# 24P_TO_15P_FPC_CSI_ADAPTER.net
KiCad netlist of a schematic drawn in Altium Designer
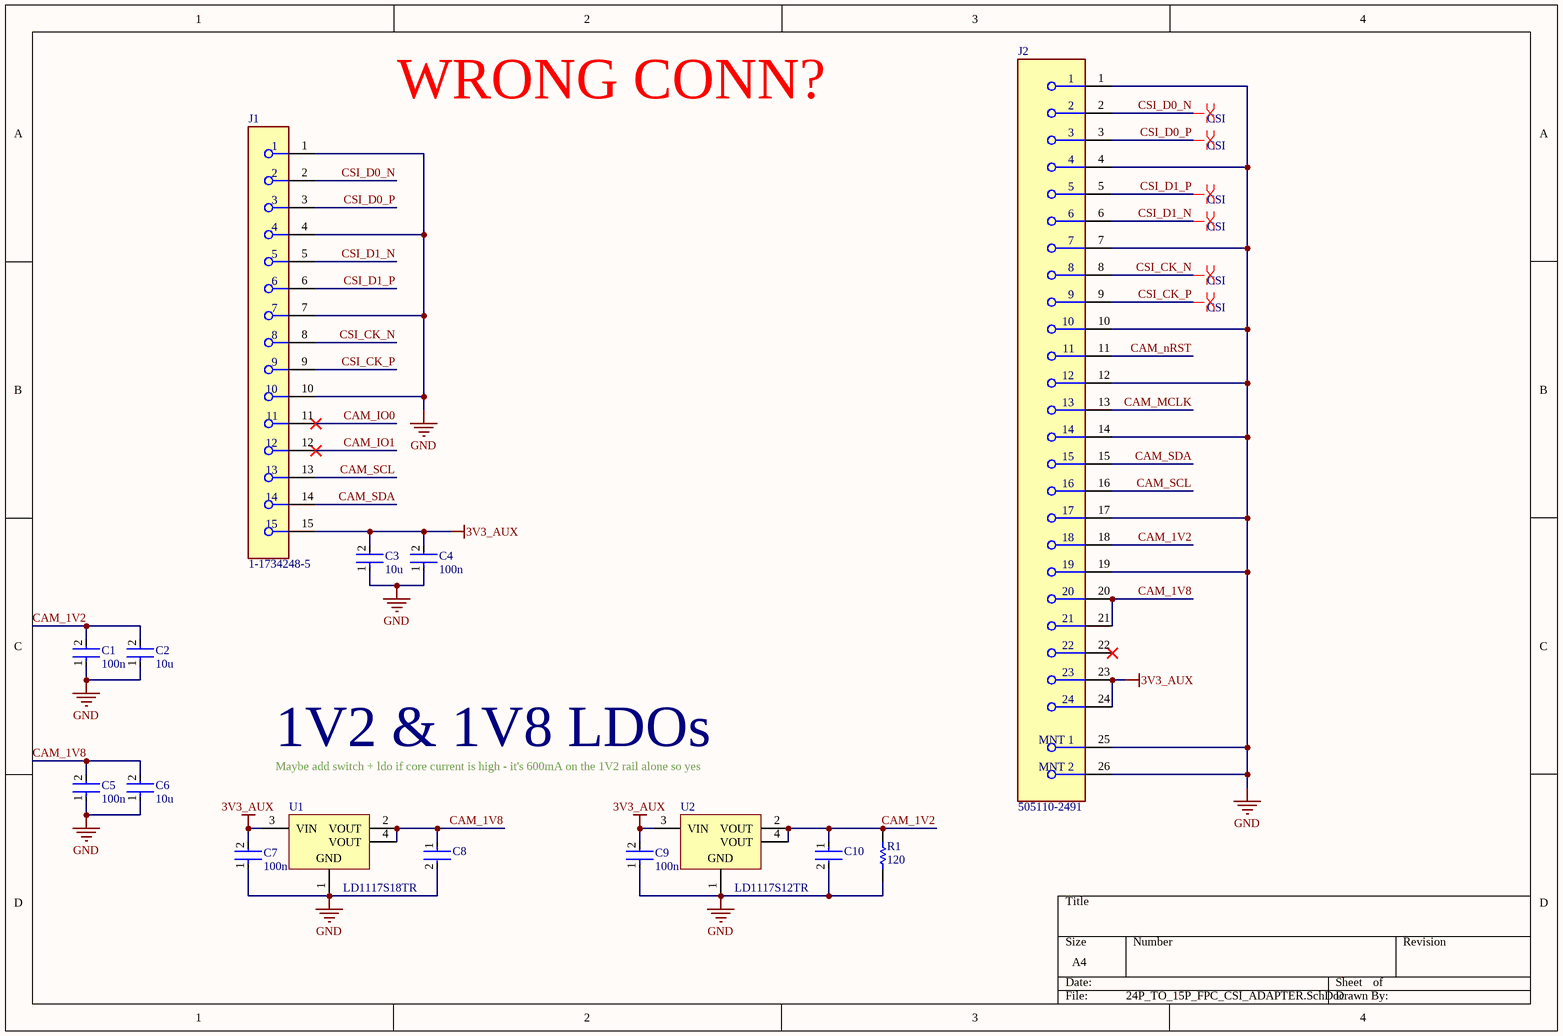
[diagram p0: 24P_TO_15P_FPC_CSI_ADAPTER.SchDoc]

(export (version "E")
  (design (tool "Eeschema 10.0.6"))
  (components
    (comp (ref "C1")
      (value "100n")
      (footprint "FP-0402-L_1_0_0_05-W_0_5-IPC_A")
      (description "LARGE PADS, 0402 CAP, CHANGE COMMENT TO MATCH REAL P/N")
      (libsource (lib "Space Concordia") (part "b4654b650e69147ec39a6b967a45e02"))
    )
    (comp (ref "C2")
      (value "10u")
      (footprint "FP-0402-L_1_0_0_05-W_0_5-IPC_A")
      (description "LARGE PADS, 0402 CAP, CHANGE COMMENT TO MATCH REAL P/N")
      (libsource (lib "Space Concordia") (part "b4654b650e69147ec39a6b967a45e02"))
    )
    (comp (ref "C3")
      (value "10u")
      (footprint "FP-0402-L_1_0_0_05-W_0_5-IPC_A")
      (description "LARGE PADS, 0402 CAP, CHANGE COMMENT TO MATCH REAL P/N")
      (libsource (lib "Space Concordia") (part "b4654b650e69147ec39a6b967a45e02"))
    )
    (comp (ref "C4")
      (value "100n")
      (footprint "FP-0402-L_1_0_0_05-W_0_5-IPC_A")
      (description "LARGE PADS, 0402 CAP, CHANGE COMMENT TO MATCH REAL P/N")
      (libsource (lib "Space Concordia") (part "b4654b650e69147ec39a6b967a45e02"))
    )
    (comp (ref "C5")
      (value "100n")
      (footprint "FP-0402-L_1_0_0_05-W_0_5-IPC_A")
      (description "LARGE PADS, 0402 CAP, CHANGE COMMENT TO MATCH REAL P/N")
      (libsource (lib "Space Concordia") (part "b4654b650e69147ec39a6b967a45e02"))
    )
    (comp (ref "C6")
      (value "10u")
      (footprint "FP-0402-L_1_0_0_05-W_0_5-IPC_A")
      (description "LARGE PADS, 0402 CAP, CHANGE COMMENT TO MATCH REAL P/N")
      (libsource (lib "Space Concordia") (part "b4654b650e69147ec39a6b967a45e02"))
    )
    (comp (ref "C7")
      (value "100n")
      (footprint "FP-0402-L_1_0_0_05-W_0_5-IPC_A")
      (description "LARGE PADS, 0402 CAP, CHANGE COMMENT TO MATCH REAL P/N")
      (libsource (lib "Space Concordia") (part "b4654b650e69147ec39a6b967a45e02"))
    )
    (comp (ref "C8")
      (value "GRM188R60J106ME47D")
      (footprint "FP-GRM188-0_1-e0_2_0_55-IPC_A")
      (description "Chip Multilayer Ceramic Capacitors for General Purpose, 0603, 10uF, X5R, 15%, 20%, 6.3V")
      (fields (field (name "VOLTAGE") "6.3V") (field (name "TOLERANCE") "20%"))
      (libsource (lib "Altium Content Vault") (part "02cd4be3c70576c341d710602a673aa"))
    )
    (comp (ref "C9")
      (value "100n")
      (footprint "FP-0402-L_1_0_0_05-W_0_5-IPC_A")
      (description "LARGE PADS, 0402 CAP, CHANGE COMMENT TO MATCH REAL P/N")
      (libsource (lib "Space Concordia") (part "b4654b650e69147ec39a6b967a45e02"))
    )
    (comp (ref "C10")
      (value "GRM188R60J106ME47D")
      (footprint "FP-GRM188-0_1-e0_2_0_55-IPC_A")
      (description "Chip Multilayer Ceramic Capacitors for General Purpose, 0603, 10uF, X5R, 15%, 20%, 6.3V")
      (fields (field (name "VOLTAGE") "6.3V") (field (name "TOLERANCE") "20%"))
      (libsource (lib "Altium Content Vault") (part "02cd4be3c70576c341d710602a673aa"))
    )
    (comp (ref "J1")
      (value "1-1734248-5")
      (footprint "FP-1-1734248-5-MFG")
      (description "CONN FPC VERT 15POS 1.00MM SMD")
      (fields
        (field (name "MANUFACTURER") "TE")
        (field (name "OCTOPART") "https://octopart.com/1-1734248-5-te+connectivity-40620898")
      )
      (libsource (lib "Altium Content Vault") (part "a0777be16b290adccad2a8f9338c195"))
    )
    (comp (ref "J2")
      (value "505110-2491")
      (footprint "FP-505110-2491-MFG")
      (description "CONN FFC/FPC BOTTOM 24P .5MM R/A")
      (libsource (lib "Altium Content Vault") (part "affe414c170fb6748ef65fd2752df84"))
    )
    (comp (ref "R1")
      (value "120")
      (footprint "R0603B")
      (description "Resistor")
      (libsource (lib "Space Concordia") (part "Resistor"))
    )
    (comp (ref "U1")
      (value "LD1117S18TR")
      (footprint "SOT-223_M")
      (description "Fixed Low Drop Positive Voltage Regulator, 1.8V, 4-Pin SOT-223, Tape and Reel")
      (libsource (lib "Altium Content Vault") (part "PM-REG-LD1117-SOT4"))
    )
    (comp (ref "U2")
      (value "LD1117S12TR")
      (footprint "SOT-223_M")
      (description "Fixed Low Drop Positive Voltage Regulator, 1.2V, 4-Pin SOT-223, Tape and Reel")
      (libsource (lib "Altium Content Vault") (part "PM-REG-LD1117-SOT4"))
    )
  )
  (nets
    (net (code "1") (name "/CAM_1V2") (class "Default")
      (node (ref "C1") (pin "2") (pinfunction "2_2") (pintype "passive"))
      (node (ref "C10") (pin "1") (pinfunction "1_1") (pintype "passive"))
      (node (ref "C2") (pin "2") (pinfunction "2_2") (pintype "passive"))
      (node (ref "J2") (pin "18") (pinfunction "18_18") (pintype "passive"))
      (node (ref "R1") (pin "2") (pinfunction "2_2") (pintype "passive"))
      (node (ref "U2") (pin "2") (pinfunction "VOUT_2") (pintype "power_in"))
      (node (ref "U2") (pin "4") (pinfunction "VOUT_4") (pintype "power_in"))
    )
    (net (code "2") (name "/CAM_1V8") (class "Default")
      (node (ref "C5") (pin "2") (pinfunction "2_2") (pintype "passive"))
      (node (ref "C6") (pin "2") (pinfunction "2_2") (pintype "passive"))
      (node (ref "C8") (pin "1") (pinfunction "1_1") (pintype "passive"))
      (node (ref "J2") (pin "20") (pinfunction "20_20") (pintype "passive"))
      (node (ref "J2") (pin "21") (pinfunction "21_21") (pintype "passive"))
      (node (ref "U1") (pin "2") (pinfunction "VOUT_2") (pintype "power_in"))
      (node (ref "U1") (pin "4") (pinfunction "VOUT_4") (pintype "power_in"))
    )
    (net (code "3") (name "/CAM_IO0") (class "Default")
      (node (ref "J1") (pin "11") (pinfunction "11_11") (pintype "passive+no_connect"))
    )
    (net (code "4") (name "/CAM_IO1") (class "Default")
      (node (ref "J1") (pin "12") (pinfunction "12_12") (pintype "passive+no_connect"))
    )
    (net (code "5") (name "/CAM_MCLK") (class "Default")
      (node (ref "J2") (pin "13") (pinfunction "13_13") (pintype "passive"))
    )
    (net (code "6") (name "/CAM_SCL") (class "Default")
      (node (ref "J1") (pin "13") (pinfunction "13_13") (pintype "passive"))
      (node (ref "J2") (pin "16") (pinfunction "16_16") (pintype "passive"))
    )
    (net (code "7") (name "/CAM_SDA") (class "Default")
      (node (ref "J1") (pin "14") (pinfunction "14_14") (pintype "passive"))
      (node (ref "J2") (pin "15") (pinfunction "15_15") (pintype "passive"))
    )
    (net (code "8") (name "/CAM_nRST") (class "Default")
      (node (ref "J2") (pin "11") (pinfunction "11_11") (pintype "passive"))
    )
    (net (code "9") (name "/CSI_CK_N") (class "Default")
      (node (ref "J1") (pin "8") (pinfunction "8_8") (pintype "passive"))
      (node (ref "J2") (pin "8") (pinfunction "8_8") (pintype "passive"))
    )
    (net (code "10") (name "/CSI_CK_P") (class "Default")
      (node (ref "J1") (pin "9") (pinfunction "9_9") (pintype "passive"))
      (node (ref "J2") (pin "9") (pinfunction "9_9") (pintype "passive"))
    )
    (net (code "11") (name "/CSI_D0_N") (class "Default")
      (node (ref "J1") (pin "2") (pinfunction "2_2") (pintype "passive"))
      (node (ref "J2") (pin "2") (pinfunction "2_2") (pintype "passive"))
    )
    (net (code "12") (name "/CSI_D0_P") (class "Default")
      (node (ref "J1") (pin "3") (pinfunction "3_3") (pintype "passive"))
      (node (ref "J2") (pin "3") (pinfunction "3_3") (pintype "passive"))
    )
    (net (code "13") (name "/CSI_D1_N") (class "Default")
      (node (ref "J1") (pin "5") (pinfunction "5_5") (pintype "passive"))
      (node (ref "J2") (pin "6") (pinfunction "6_6") (pintype "passive"))
    )
    (net (code "14") (name "/CSI_D1_P") (class "Default")
      (node (ref "J1") (pin "6") (pinfunction "6_6") (pintype "passive"))
      (node (ref "J2") (pin "5") (pinfunction "5_5") (pintype "passive"))
    )
    (net (code "15") (name "3V3_AUX") (class "Default")
      (node (ref "C3") (pin "2") (pinfunction "2_2") (pintype "passive"))
      (node (ref "C4") (pin "2") (pinfunction "2_2") (pintype "passive"))
      (node (ref "C7") (pin "2") (pinfunction "2_2") (pintype "passive"))
      (node (ref "C9") (pin "2") (pinfunction "2_2") (pintype "passive"))
      (node (ref "J1") (pin "15") (pinfunction "15_15") (pintype "passive"))
      (node (ref "J2") (pin "23") (pinfunction "23_23") (pintype "passive"))
      (node (ref "J2") (pin "24") (pinfunction "24_24") (pintype "passive"))
      (node (ref "U1") (pin "3") (pinfunction "VIN_3") (pintype "power_in"))
      (node (ref "U2") (pin "3") (pinfunction "VIN_3") (pintype "power_in"))
    )
    (net (code "16") (name "GND") (class "Default")
      (node (ref "C1") (pin "1") (pinfunction "1_1") (pintype "passive"))
      (node (ref "C10") (pin "2") (pinfunction "2_2") (pintype "passive"))
      (node (ref "C2") (pin "1") (pinfunction "1_1") (pintype "passive"))
      (node (ref "C3") (pin "1") (pinfunction "1_1") (pintype "passive"))
      (node (ref "C4") (pin "1") (pinfunction "1_1") (pintype "passive"))
      (node (ref "C5") (pin "1") (pinfunction "1_1") (pintype "passive"))
      (node (ref "C6") (pin "1") (pinfunction "1_1") (pintype "passive"))
      (node (ref "C7") (pin "1") (pinfunction "1_1") (pintype "passive"))
      (node (ref "C8") (pin "2") (pinfunction "2_2") (pintype "passive"))
      (node (ref "C9") (pin "1") (pinfunction "1_1") (pintype "passive"))
      (node (ref "J1") (pin "1") (pinfunction "1_1") (pintype "passive"))
      (node (ref "J1") (pin "10") (pinfunction "10_10") (pintype "passive"))
      (node (ref "J1") (pin "4") (pinfunction "4_4") (pintype "passive"))
      (node (ref "J1") (pin "7") (pinfunction "7_7") (pintype "passive"))
      (node (ref "J2") (pin "1") (pinfunction "1_1") (pintype "passive"))
      (node (ref "J2") (pin "10") (pinfunction "10_10") (pintype "passive"))
      (node (ref "J2") (pin "12") (pinfunction "12_12") (pintype "passive"))
      (node (ref "J2") (pin "14") (pinfunction "14_14") (pintype "passive"))
      (node (ref "J2") (pin "17") (pinfunction "17_17") (pintype "passive"))
      (node (ref "J2") (pin "19") (pinfunction "19_19") (pintype "passive"))
      (node (ref "J2") (pin "25") (pinfunction "MNT_1_25") (pintype "passive"))
      (node (ref "J2") (pin "26") (pinfunction "MNT_2_26") (pintype "passive"))
      (node (ref "J2") (pin "4") (pinfunction "4_4") (pintype "passive"))
      (node (ref "J2") (pin "7") (pinfunction "7_7") (pintype "passive"))
      (node (ref "R1") (pin "1") (pinfunction "1_1") (pintype "passive"))
      (node (ref "U1") (pin "1") (pinfunction "GND_1") (pintype "power_in"))
      (node (ref "U2") (pin "1") (pinfunction "GND_1") (pintype "power_in"))
    )
    (net (code "17") (name "unconnected-(J2-Pad22)") (class "Default")
      (node (ref "J2") (pin "22") (pinfunction "22_22") (pintype "passive+no_connect"))
    )
  )
)
